# Bluetooth.net
KiCad netlist of a schematic drawn in Altium Designer
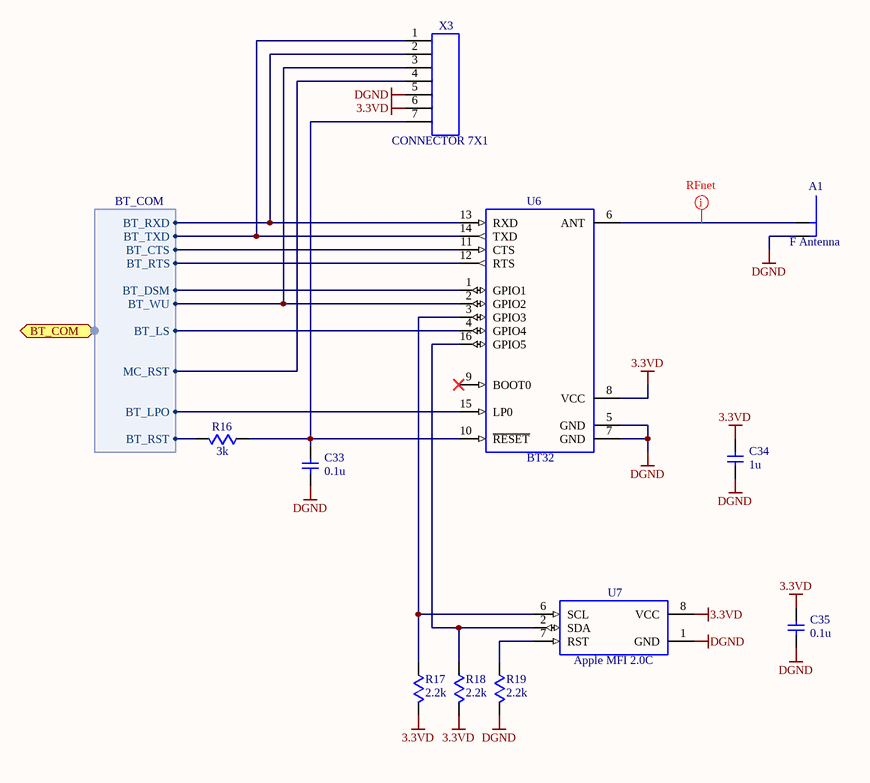
[diagram p0: Bluetooth.SchDoc]

(export (version "E")
  (design (tool "Eeschema 10.0.6"))
  (components
    (comp (ref "A1")
      (value "F Antenna")
      (footprint "PCB inverted F antenna mirror")
      (libsource (lib "My_lib") (part "F Antenna"))
    )
    (comp (ref "C33") (value "0.1u") (footprint "SMD/C/0603") (libsource (lib "My_lib") (part "Capacitor")))
    (comp (ref "C34") (value "1u") (footprint "SMD/C/0603") (libsource (lib "My_lib") (part "Capacitor")))
    (comp (ref "C35") (value "0.1u") (footprint "SMD/C/0603") (libsource (lib "My_lib") (part "Capacitor")))
    (comp (ref "R16") (value "3k") (footprint "SMD/R/0603") (libsource (lib "My_lib") (part "Resistor")))
    (comp (ref "R17") (value "2.2k") (footprint "SMD/R/0603") (libsource (lib "My_lib") (part "Resistor")))
    (comp (ref "R18") (value "2.2k") (footprint "SMD/R/0603") (libsource (lib "My_lib") (part "Resistor")))
    (comp (ref "R19") (value "2.2k") (footprint "SMD/R/0603") (libsource (lib "My_lib") (part "Resistor")))
    (comp (ref "U6")
      (value "BT32")
      (footprint "BT32")
      (description "Bluetooth module")
      (libsource (lib "My_lib") (part "BT32"))
    )
    (comp (ref "U7")
      (value "Apple MFI 2.0C")
      (footprint "Apple MFI 2.0C")
      (description "Apple Authentication Coprocessor 2.0C")
      (libsource (lib "My_lib") (part "Apple MFI 2.0C"))
    )
    (comp (ref "X3")
      (value "CONNECTOR 7X1")
      (footprint "CONNECTOR/IDC/0.05P/1X7")
      (libsource (lib "My_lib") (part "CONNECTOR 7X1"))
    )
  )
  (nets
    (net (code "2") (name "/BT_CTS") (class "Default")
      (node (ref "U6") (pin "11") (pinfunction "CTS_11") (pintype "input"))
    )
    (net (code "3") (name "/BT_DSM") (class "Default")
      (node (ref "U6") (pin "1") (pinfunction "GPIO1_1") (pintype "bidirectional"))
    )
    (net (code "4") (name "/BT_LPO") (class "Default")
      (node (ref "U6") (pin "15") (pinfunction "LP0_15") (pintype "input"))
    )
    (net (code "5") (name "/BT_LS") (class "Default")
      (node (ref "U6") (pin "4") (pinfunction "GPIO4_4") (pintype "bidirectional"))
    )
    (net (code "6") (name "/BT_RST") (class "Default")
      (node (ref "R16") (pin "2") (pinfunction "2_2") (pintype "passive"))
    )
    (net (code "7") (name "/BT_RTS") (class "Default")
      (node (ref "U6") (pin "12") (pinfunction "RTS_12") (pintype "output"))
    )
    (net (code "8") (name "/BT_RXD") (class "Default")
      (node (ref "U6") (pin "13") (pinfunction "RXD_13") (pintype "input"))
      (node (ref "X3") (pin "2") (pinfunction "2_2") (pintype "passive"))
    )
    (net (code "9") (name "/BT_TXD") (class "Default")
      (node (ref "U6") (pin "14") (pinfunction "TXD_14") (pintype "output"))
      (node (ref "X3") (pin "1") (pinfunction "1_1") (pintype "passive"))
    )
    (net (code "10") (name "/BT_WU") (class "Default")
      (node (ref "U6") (pin "2") (pinfunction "GPIO2_2") (pintype "bidirectional"))
      (node (ref "X3") (pin "3") (pinfunction "3_3") (pintype "passive"))
    )
    (net (code "11") (name "/MC_RST") (class "Default")
      (node (ref "X3") (pin "4") (pinfunction "4_4") (pintype "passive"))
    )
    (net (code "13") (name "3.3VD") (class "Default")
      (node (ref "C34") (pin "2") (pinfunction "2_2") (pintype "passive"))
      (node (ref "C35") (pin "2") (pinfunction "2_2") (pintype "passive"))
      (node (ref "R17") (pin "2") (pinfunction "2_2") (pintype "passive"))
      (node (ref "R18") (pin "2") (pinfunction "2_2") (pintype "passive"))
      (node (ref "U6") (pin "8") (pinfunction "VCC_8") (pintype "power_in"))
      (node (ref "U7") (pin "8") (pinfunction "VCC_8") (pintype "power_in"))
      (node (ref "X3") (pin "6") (pinfunction "6_6") (pintype "passive"))
    )
    (net (code "14") (name "DGND") (class "Default")
      (node (ref "A1") (pin "2") (pinfunction "2_2") (pintype "passive"))
      (node (ref "C33") (pin "1") (pinfunction "1_1") (pintype "passive"))
      (node (ref "C34") (pin "1") (pinfunction "1_1") (pintype "passive"))
      (node (ref "C35") (pin "1") (pinfunction "1_1") (pintype "passive"))
      (node (ref "R19") (pin "2") (pinfunction "2_2") (pintype "passive"))
      (node (ref "U6") (pin "5") (pinfunction "GND_5") (pintype "power_in"))
      (node (ref "U6") (pin "7") (pinfunction "GND_7") (pintype "power_in"))
      (node (ref "U7") (pin "1") (pinfunction "GND_1") (pintype "power_in"))
      (node (ref "X3") (pin "5") (pinfunction "5_5") (pintype "passive"))
    )
    (net (code "15") (name "Net-(U6-ANT)") (class "Default")
      (node (ref "A1") (pin "1") (pinfunction "1_1") (pintype "passive"))
      (node (ref "U6") (pin "6") (pinfunction "ANT_6") (pintype "power_in"))
    )
    (net (code "16") (name "Net-(U6-GPIO3)") (class "Default")
      (node (ref "R17") (pin "1") (pinfunction "1_1") (pintype "passive"))
      (node (ref "U6") (pin "3") (pinfunction "GPIO3_3") (pintype "bidirectional"))
      (node (ref "U7") (pin "6") (pinfunction "SCL_6") (pintype "input"))
    )
    (net (code "17") (name "Net-(U6-GPIO5)") (class "Default")
      (node (ref "R18") (pin "1") (pinfunction "1_1") (pintype "passive"))
      (node (ref "U6") (pin "16") (pinfunction "GPIO5_16") (pintype "bidirectional"))
      (node (ref "U7") (pin "2") (pinfunction "SDA_2") (pintype "bidirectional"))
    )
    (net (code "18") (name "Net-(U6-~{RESET})") (class "Default")
      (node (ref "C33") (pin "2") (pinfunction "2_2") (pintype "passive"))
      (node (ref "R16") (pin "1") (pinfunction "1_1") (pintype "passive"))
      (node (ref "U6") (pin "10") (pinfunction "~{RESET}_10") (pintype "input"))
      (node (ref "X3") (pin "7") (pinfunction "7_7") (pintype "passive"))
    )
    (net (code "19") (name "Net-(U7-RST)") (class "Default")
      (node (ref "R19") (pin "1") (pinfunction "1_1") (pintype "passive"))
      (node (ref "U7") (pin "7") (pinfunction "RST_7") (pintype "input"))
    )
    (net (code "20") (name "unconnected-(U6-BOOT0-Pad9)") (class "Default")
      (node (ref "U6") (pin "9") (pinfunction "BOOT0_9") (pintype "input+no_connect"))
    )
  )
)
